# birthdaycontrol.net
KiCad netlist of a schematic drawn in EAGLE
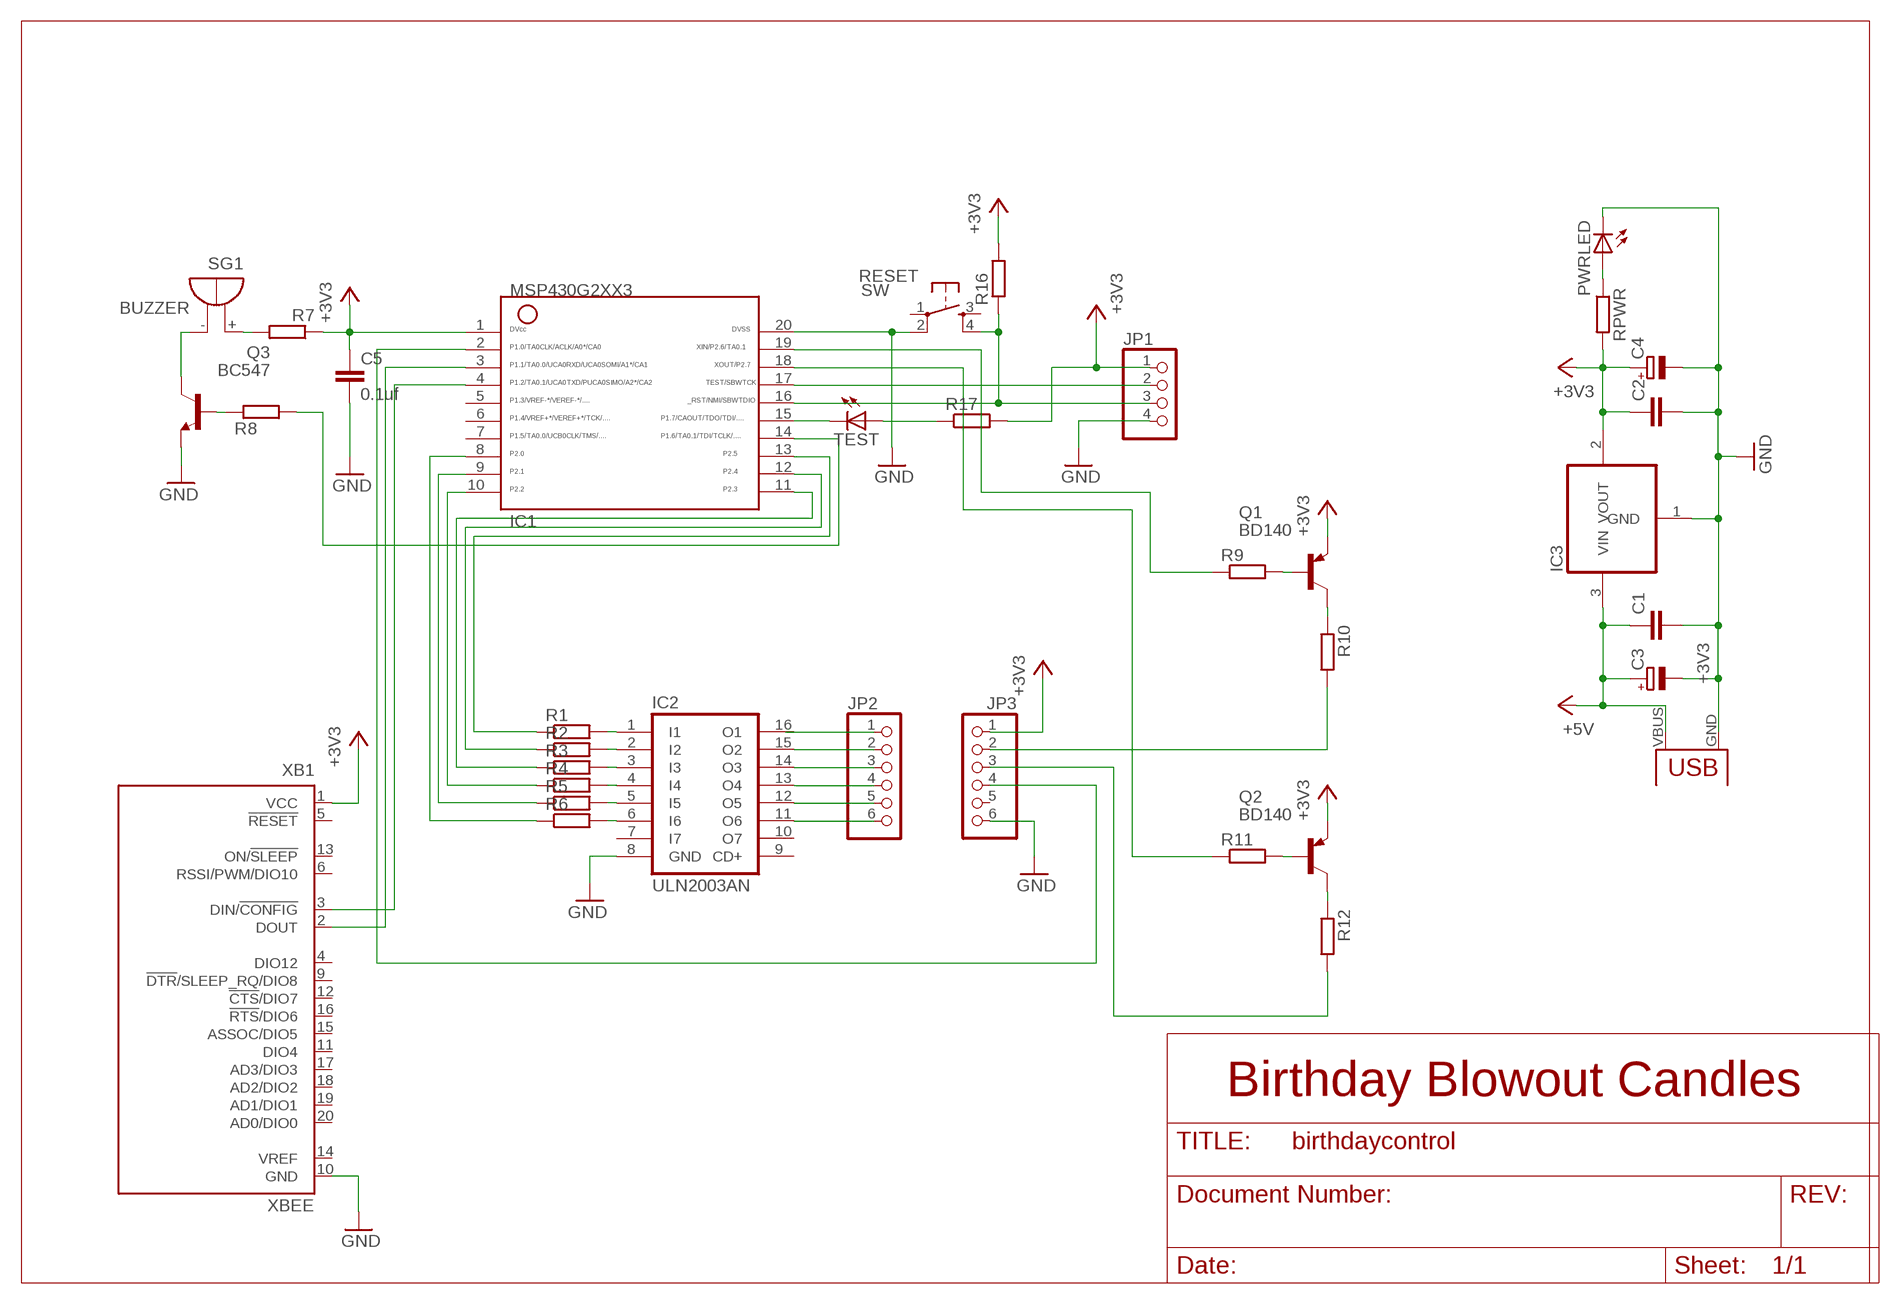
[diagram p0: schematic, sheet 1]

(export (version "E")
  (design (tool "Eeschema 10.0.6"))
  (components
    (comp (ref "C1")
      (value "C-EU025-025X050")
      (footprint "eagle-import:C025-025X050")
      (libsource (lib "eagle-import") (part "C-EU025-025X050"))
    )
    (comp (ref "C2")
      (value "C-EU025-025X050")
      (footprint "eagle-import:C025-025X050")
      (libsource (lib "eagle-import") (part "C-EU025-025X050"))
    )
    (comp (ref "C3")
      (value "CPOL-EUE2.5-5")
      (footprint "eagle-import:E2,5-5")
      (libsource (lib "eagle-import") (part "CPOL-EUE2.5-5"))
    )
    (comp (ref "C4")
      (value "CPOL-EUE2.5-5")
      (footprint "eagle-import:E2,5-5")
      (libsource (lib "eagle-import") (part "CPOL-EUE2.5-5"))
    )
    (comp (ref "C5")
      (value "0.1uf")
      (footprint "eagle-import:C025-025X050")
      (libsource (lib "eagle-import") (part "C-EU025-025X050"))
    )
    (comp (ref "IC1")
      (value "MSP430")
      (footprint "eagle-import:G2553-DIP20")
      (libsource (lib "eagle-import") (part "MSP430G2553DIP20"))
    )
    (comp (ref "IC2")
      (value "ULN2003AN")
      (footprint "eagle-import:DIL16")
      (libsource (lib "eagle-import") (part "ULN2003AN"))
    )
    (comp (ref "IC3")
      (value "REG1117")
      (footprint "eagle-import:SOT223")
      (libsource (lib "eagle-import") (part "REG1117"))
    )
    (comp (ref "JP1")
      (value "PINHD-1X4")
      (footprint "eagle-import:1X04")
      (libsource (lib "eagle-import") (part "PINHD-1X4"))
    )
    (comp (ref "JP2")
      (value "PINHD-1X6")
      (footprint "eagle-import:1X06")
      (libsource (lib "eagle-import") (part "PINHD-1X6"))
    )
    (comp (ref "JP3")
      (value "PINHD-1X6")
      (footprint "eagle-import:1X06")
      (libsource (lib "eagle-import") (part "PINHD-1X6"))
    )
    (comp (ref "PWRLED")
      (value "LED3MM")
      (footprint "eagle-import:LED3MM")
      (libsource (lib "eagle-import") (part "LED3MM"))
    )
    (comp (ref "Q1")
      (value "BD140")
      (footprint "eagle-import:TO126")
      (libsource (lib "eagle-import") (part "BD140"))
    )
    (comp (ref "Q2")
      (value "BD140")
      (footprint "eagle-import:TO126")
      (libsource (lib "eagle-import") (part "BD140"))
    )
    (comp (ref "Q3")
      (value "BC547")
      (footprint "eagle-import:TO92")
      (libsource (lib "eagle-import") (part "BC547"))
    )
    (comp (ref "R1")
      (value "R-EU_0207/7")
      (footprint "eagle-import:0207_7")
      (libsource (lib "eagle-import") (part "resistor_R-EU_0207/7"))
    )
    (comp (ref "R2")
      (value "R-EU_0207/7")
      (footprint "eagle-import:0207_7")
      (libsource (lib "eagle-import") (part "resistor_R-EU_0207/7"))
    )
    (comp (ref "R3")
      (value "R-EU_0207/7")
      (footprint "eagle-import:0207_7")
      (libsource (lib "eagle-import") (part "resistor_R-EU_0207/7"))
    )
    (comp (ref "R4")
      (value "R-EU_0207/7")
      (footprint "eagle-import:0207_7")
      (libsource (lib "eagle-import") (part "resistor_R-EU_0207/7"))
    )
    (comp (ref "R5")
      (value "R-EU_0207/7")
      (footprint "eagle-import:0207_7")
      (libsource (lib "eagle-import") (part "resistor_R-EU_0207/7"))
    )
    (comp (ref "R6")
      (value "R-EU_0207/7")
      (footprint "eagle-import:0207_7")
      (libsource (lib "eagle-import") (part "resistor_R-EU_0207/7"))
    )
    (comp (ref "R7")
      (value "R-EU_0207/7")
      (footprint "eagle-import:0207_7")
      (libsource (lib "eagle-import") (part "R-EU_0207/7"))
    )
    (comp (ref "R8")
      (value "R-EU_0207/7")
      (footprint "eagle-import:0207_7")
      (libsource (lib "eagle-import") (part "R-EU_0207/7"))
    )
    (comp (ref "R9")
      (value "R-EU_0207/7")
      (footprint "eagle-import:0207_7")
      (libsource (lib "eagle-import") (part "R-EU_0207/7"))
    )
    (comp (ref "R10")
      (value "R-EU_0207/7")
      (footprint "eagle-import:0207_7")
      (libsource (lib "eagle-import") (part "R-EU_0207/7"))
    )
    (comp (ref "R11")
      (value "R-EU_0207/7")
      (footprint "eagle-import:0207_7")
      (libsource (lib "eagle-import") (part "R-EU_0207/7"))
    )
    (comp (ref "R12")
      (value "R-EU_0207/7")
      (footprint "eagle-import:0207_7")
      (libsource (lib "eagle-import") (part "R-EU_0207/7"))
    )
    (comp (ref "R16")
      (value "R-EU_0207/7")
      (footprint "eagle-import:0207_7")
      (libsource (lib "eagle-import") (part "R-EU_0207/7"))
    )
    (comp (ref "R17")
      (value "R-EU_0207/7")
      (footprint "eagle-import:0207_7")
      (libsource (lib "eagle-import") (part "R-EU_0207/7"))
    )
    (comp (ref "RESET")
      (value "SW")
      (footprint "eagle-import:B3F-10XX")
      (libsource (lib "eagle-import") (part "OMRON_SWITCH_10-XX"))
    )
    (comp (ref "RPWR")
      (value "R-EU_0207/7")
      (footprint "eagle-import:0207_7")
      (libsource (lib "eagle-import") (part "R-EU_0207/7"))
    )
    (comp (ref "SG1")
      (value "BUZZER")
      (footprint "eagle-import:F_TMB")
      (libsource (lib "eagle-import") (part "BUZZER"))
    )
    (comp (ref "TEST")
      (value "LED3MM")
      (footprint "eagle-import:LED3MM")
      (libsource (lib "eagle-import") (part "LED3MM"))
    )
    (comp (ref "U$6")
      (value "USB(POWER)")
      (footprint "eagle-import:USB(POWER)")
      (libsource (lib "eagle-import") (part "USB(POWER)"))
    )
    (comp (ref "XB1")
      (value "XBEE")
      (footprint "eagle-import:XBEE")
      (fields (field (name "MPN") "XBP24-Z7UIT-004"))
      (libsource (lib "eagle-import") (part "XBEE"))
    )
  )
  (nets
    (net (code "1") (name "+3V3") (class "Default")
      (node (ref "C2") (pin "1") (pinfunction "1_1") (pintype "passive"))
      (node (ref "C4") (pin "+") (pinfunction "+_+") (pintype "passive"))
      (node (ref "C5") (pin "1") (pinfunction "1_1") (pintype "passive"))
      (node (ref "IC1") (pin "1") (pinfunction "1_1") (pintype "power_in"))
      (node (ref "IC3") (pin "2") (pinfunction "VOUT_2") (pintype "output"))
      (node (ref "JP1") (pin "1") (pinfunction "1_1") (pintype "passive"))
      (node (ref "JP3") (pin "1") (pinfunction "1_1") (pintype "passive"))
      (node (ref "Q1") (pin "1") (pinfunction "E_1") (pintype "passive"))
      (node (ref "Q2") (pin "1") (pinfunction "E_1") (pintype "passive"))
      (node (ref "R16") (pin "2") (pinfunction "2_2") (pintype "passive"))
      (node (ref "R17") (pin "2") (pinfunction "2_2") (pintype "passive"))
      (node (ref "R7") (pin "1") (pinfunction "1_1") (pintype "passive"))
      (node (ref "RPWR") (pin "2") (pinfunction "2_2") (pintype "passive"))
      (node (ref "XB1") (pin "1") (pinfunction "VCC_1") (pintype "power_in"))
    )
    (net (code "2") (name "+5V") (class "Default")
      (node (ref "C1") (pin "1") (pinfunction "1_1") (pintype "passive"))
      (node (ref "C3") (pin "+") (pinfunction "+_+") (pintype "passive"))
      (node (ref "IC3") (pin "3") (pinfunction "VIN_3") (pintype "input"))
      (node (ref "U$6") (pin "VBUS") (pinfunction "VCC_VBUS") (pintype "power_in"))
    )
    (net (code "3") (name "GND") (class "Default")
      (node (ref "C1") (pin "2") (pinfunction "2_2") (pintype "passive"))
      (node (ref "C2") (pin "2") (pinfunction "2_2") (pintype "passive"))
      (node (ref "C3") (pin "-") (pinfunction "-_-") (pintype "passive"))
      (node (ref "C4") (pin "-") (pinfunction "-_-") (pintype "passive"))
      (node (ref "C5") (pin "2") (pinfunction "2_2") (pintype "passive"))
      (node (ref "IC1") (pin "20") (pinfunction "20_20") (pintype "power_in"))
      (node (ref "IC2") (pin "8") (pinfunction "GND_8") (pintype "power_in"))
      (node (ref "IC3") (pin "1") (pinfunction "GND_1") (pintype "power_in"))
      (node (ref "JP1") (pin "4") (pinfunction "4_4") (pintype "passive"))
      (node (ref "JP3") (pin "6") (pinfunction "6_6") (pintype "passive"))
      (node (ref "PWRLED") (pin "K") (pinfunction "C_K") (pintype "passive"))
      (node (ref "Q3") (pin "1") (pinfunction "E_1") (pintype "passive"))
      (node (ref "RESET") (pin "2") (pinfunction "P1_2") (pintype "passive"))
      (node (ref "U$6") (pin "GND") (pinfunction "GND_GND") (pintype "power_in"))
      (node (ref "XB1") (pin "10") (pinfunction "GND_10") (pintype "power_in"))
    )
    (net (code "4") (name "Net-(IC1-Pad2)") (class "Default")
      (node (ref "IC1") (pin "2") (pinfunction "2_2") (pintype "bidirectional"))
      (node (ref "JP3") (pin "4") (pinfunction "4_4") (pintype "passive"))
    )
    (net (code "5") (name "Net-(IC1-Pad8)") (class "Default")
      (node (ref "IC1") (pin "8") (pinfunction "8_8") (pintype "bidirectional"))
      (node (ref "R6") (pin "1") (pinfunction "1_1") (pintype "passive"))
    )
    (net (code "6") (name "Net-(IC1-Pad9)") (class "Default")
      (node (ref "IC1") (pin "9") (pinfunction "9_9") (pintype "bidirectional"))
      (node (ref "R5") (pin "1") (pinfunction "1_1") (pintype "passive"))
    )
    (net (code "7") (name "Net-(IC1-Pad10)") (class "Default")
      (node (ref "IC1") (pin "10") (pinfunction "10_10") (pintype "bidirectional"))
      (node (ref "R4") (pin "1") (pinfunction "1_1") (pintype "passive"))
    )
    (net (code "8") (name "Net-(IC1-Pad11)") (class "Default")
      (node (ref "IC1") (pin "11") (pinfunction "11_11") (pintype "bidirectional"))
      (node (ref "R3") (pin "1") (pinfunction "1_1") (pintype "passive"))
    )
    (net (code "9") (name "Net-(IC1-Pad12)") (class "Default")
      (node (ref "IC1") (pin "12") (pinfunction "12_12") (pintype "bidirectional"))
      (node (ref "R2") (pin "1") (pinfunction "1_1") (pintype "passive"))
    )
    (net (code "10") (name "Net-(IC1-Pad13)") (class "Default")
      (node (ref "IC1") (pin "13") (pinfunction "13_13") (pintype "bidirectional"))
      (node (ref "R1") (pin "1") (pinfunction "1_1") (pintype "passive"))
    )
    (net (code "11") (name "Net-(IC1-Pad14)") (class "Default")
      (node (ref "IC1") (pin "14") (pinfunction "14_14") (pintype "bidirectional"))
      (node (ref "R8") (pin "2") (pinfunction "2_2") (pintype "passive"))
    )
    (net (code "12") (name "Net-(IC1-Pad17)") (class "Default")
      (node (ref "IC1") (pin "17") (pinfunction "17_17") (pintype "bidirectional"))
      (node (ref "JP1") (pin "2") (pinfunction "2_2") (pintype "passive"))
    )
    (net (code "13") (name "Net-(IC1-Pad18)") (class "Default")
      (node (ref "IC1") (pin "18") (pinfunction "18_18") (pintype "bidirectional"))
      (node (ref "R11") (pin "1") (pinfunction "1_1") (pintype "passive"))
    )
    (net (code "14") (name "Net-(IC1-Pad19)") (class "Default")
      (node (ref "IC1") (pin "19") (pinfunction "19_19") (pintype "bidirectional"))
      (node (ref "R9") (pin "1") (pinfunction "1_1") (pintype "passive"))
    )
    (net (code "15") (name "Net-(IC2-I1)") (class "Default")
      (node (ref "IC2") (pin "1") (pinfunction "I1_1") (pintype "input"))
      (node (ref "R1") (pin "2") (pinfunction "2_2") (pintype "passive"))
    )
    (net (code "16") (name "Net-(IC2-I2)") (class "Default")
      (node (ref "IC2") (pin "2") (pinfunction "I2_2") (pintype "input"))
      (node (ref "R2") (pin "2") (pinfunction "2_2") (pintype "passive"))
    )
    (net (code "17") (name "Net-(IC2-I3)") (class "Default")
      (node (ref "IC2") (pin "3") (pinfunction "I3_3") (pintype "input"))
      (node (ref "R3") (pin "2") (pinfunction "2_2") (pintype "passive"))
    )
    (net (code "18") (name "Net-(IC2-I4)") (class "Default")
      (node (ref "IC2") (pin "4") (pinfunction "I4_4") (pintype "input"))
      (node (ref "R4") (pin "2") (pinfunction "2_2") (pintype "passive"))
    )
    (net (code "19") (name "Net-(IC2-I5)") (class "Default")
      (node (ref "IC2") (pin "5") (pinfunction "I5_5") (pintype "input"))
      (node (ref "R5") (pin "2") (pinfunction "2_2") (pintype "passive"))
    )
    (net (code "20") (name "Net-(IC2-I6)") (class "Default")
      (node (ref "IC2") (pin "6") (pinfunction "I6_6") (pintype "input"))
      (node (ref "R6") (pin "2") (pinfunction "2_2") (pintype "passive"))
    )
    (net (code "21") (name "Net-(IC2-O1)") (class "Default")
      (node (ref "IC2") (pin "16") (pinfunction "O1_16") (pintype "open_collector"))
      (node (ref "JP2") (pin "1") (pinfunction "1_1") (pintype "passive"))
    )
    (net (code "22") (name "Net-(IC2-O2)") (class "Default")
      (node (ref "IC2") (pin "15") (pinfunction "O2_15") (pintype "open_collector"))
      (node (ref "JP2") (pin "2") (pinfunction "2_2") (pintype "passive"))
    )
    (net (code "23") (name "Net-(IC2-O3)") (class "Default")
      (node (ref "IC2") (pin "14") (pinfunction "O3_14") (pintype "open_collector"))
      (node (ref "JP2") (pin "3") (pinfunction "3_3") (pintype "passive"))
    )
    (net (code "24") (name "Net-(IC2-O4)") (class "Default")
      (node (ref "IC2") (pin "13") (pinfunction "O4_13") (pintype "open_collector"))
      (node (ref "JP2") (pin "4") (pinfunction "4_4") (pintype "passive"))
    )
    (net (code "25") (name "Net-(IC2-O5)") (class "Default")
      (node (ref "IC2") (pin "12") (pinfunction "O5_12") (pintype "open_collector"))
      (node (ref "JP2") (pin "5") (pinfunction "5_5") (pintype "passive"))
    )
    (net (code "26") (name "Net-(IC2-O6)") (class "Default")
      (node (ref "IC2") (pin "11") (pinfunction "O6_11") (pintype "open_collector"))
      (node (ref "JP2") (pin "6") (pinfunction "6_6") (pintype "passive"))
    )
    (net (code "27") (name "Net-(JP3-Pad2)") (class "Default")
      (node (ref "JP3") (pin "2") (pinfunction "2_2") (pintype "passive"))
      (node (ref "R10") (pin "2") (pinfunction "2_2") (pintype "passive"))
    )
    (net (code "28") (name "Net-(JP3-Pad3)") (class "Default")
      (node (ref "JP3") (pin "3") (pinfunction "3_3") (pintype "passive"))
      (node (ref "R12") (pin "2") (pinfunction "2_2") (pintype "passive"))
    )
    (net (code "29") (name "Net-(PWRLED-PadA)") (class "Default")
      (node (ref "PWRLED") (pin "A") (pinfunction "A_A") (pintype "passive"))
      (node (ref "RPWR") (pin "1") (pinfunction "1_1") (pintype "passive"))
    )
    (net (code "30") (name "Net-(Q1-B)") (class "Default")
      (node (ref "Q1") (pin "3") (pinfunction "B_3") (pintype "passive"))
      (node (ref "R9") (pin "2") (pinfunction "2_2") (pintype "passive"))
    )
    (net (code "31") (name "Net-(Q1-C)") (class "Default")
      (node (ref "Q1") (pin "2") (pinfunction "C_2") (pintype "passive"))
      (node (ref "R10") (pin "1") (pinfunction "1_1") (pintype "passive"))
    )
    (net (code "32") (name "Net-(Q2-B)") (class "Default")
      (node (ref "Q2") (pin "3") (pinfunction "B_3") (pintype "passive"))
      (node (ref "R11") (pin "2") (pinfunction "2_2") (pintype "passive"))
    )
    (net (code "33") (name "Net-(Q2-C)") (class "Default")
      (node (ref "Q2") (pin "2") (pinfunction "C_2") (pintype "passive"))
      (node (ref "R12") (pin "1") (pinfunction "1_1") (pintype "passive"))
    )
    (net (code "34") (name "Net-(Q3-B)") (class "Default")
      (node (ref "Q3") (pin "2") (pinfunction "B_2") (pintype "passive"))
      (node (ref "R8") (pin "1") (pinfunction "1_1") (pintype "passive"))
    )
    (net (code "35") (name "Net-(Q3-C)") (class "Default")
      (node (ref "Q3") (pin "3") (pinfunction "C_3") (pintype "passive"))
      (node (ref "SG1") (pin "-") (pinfunction "-_-") (pintype "passive"))
    )
    (net (code "36") (name "Net-(R7-Pad2)") (class "Default")
      (node (ref "R7") (pin "2") (pinfunction "2_2") (pintype "passive"))
      (node (ref "SG1") (pin "+") (pinfunction "+_+") (pintype "passive"))
    )
    (net (code "37") (name "Net-(R17-Pad1)") (class "Default")
      (node (ref "R17") (pin "1") (pinfunction "1_1") (pintype "passive"))
      (node (ref "TEST") (pin "A") (pinfunction "A_A") (pintype "passive"))
    )
    (net (code "38") (name "Net-(RESET-S1)") (class "Default")
      (node (ref "IC1") (pin "16") (pinfunction "16_16") (pintype "bidirectional"))
      (node (ref "JP1") (pin "3") (pinfunction "3_3") (pintype "passive"))
      (node (ref "R16") (pin "1") (pinfunction "1_1") (pintype "passive"))
      (node (ref "RESET") (pin "4") (pinfunction "S1_4") (pintype "passive"))
    )
    (net (code "39") (name "Net-(TEST-C)") (class "Default")
      (node (ref "IC1") (pin "15") (pinfunction "15_15") (pintype "bidirectional"))
      (node (ref "TEST") (pin "K") (pinfunction "C_K") (pintype "passive"))
    )
    (net (code "40") (name "Net-(XB1-DIN{slash}~{CONFIG})") (class "Default")
      (node (ref "IC1") (pin "4") (pinfunction "4_4") (pintype "bidirectional"))
      (node (ref "XB1") (pin "3") (pinfunction "DIN/~{CONFIG}_3") (pintype "input"))
    )
    (net (code "41") (name "Net-(XB1-DOUT)") (class "Default")
      (node (ref "IC1") (pin "3") (pinfunction "3_3") (pintype "bidirectional"))
      (node (ref "XB1") (pin "2") (pinfunction "DOUT_2") (pintype "output"))
    )
    (net (code "42") (name "unconnected-(IC1-Pad5)") (class "Default")
      (node (ref "IC1") (pin "5") (pinfunction "5_5") (pintype "bidirectional"))
    )
    (net (code "43") (name "unconnected-(IC1-Pad6)") (class "Default")
      (node (ref "IC1") (pin "6") (pinfunction "6_6") (pintype "bidirectional"))
    )
    (net (code "44") (name "unconnected-(IC1-Pad7)") (class "Default")
      (node (ref "IC1") (pin "7") (pinfunction "7_7") (pintype "bidirectional"))
    )
    (net (code "45") (name "unconnected-(IC2-CD+-Pad9)") (class "Default")
      (node (ref "IC2") (pin "9") (pinfunction "CD+_9") (pintype "passive"))
    )
    (net (code "46") (name "unconnected-(IC2-I7-Pad7)") (class "Default")
      (node (ref "IC2") (pin "7") (pinfunction "I7_7") (pintype "input"))
    )
    (net (code "47") (name "unconnected-(IC2-O7-Pad10)") (class "Default")
      (node (ref "IC2") (pin "10") (pinfunction "O7_10") (pintype "open_collector"))
    )
    (net (code "48") (name "unconnected-(JP3-Pad5)") (class "Default")
      (node (ref "JP3") (pin "5") (pinfunction "5_5") (pintype "passive"))
    )
    (net (code "49") (name "unconnected-(RESET-P-Pad1)") (class "Default")
      (node (ref "RESET") (pin "1") (pinfunction "P_1") (pintype "passive"))
    )
    (net (code "50") (name "unconnected-(RESET-S-Pad3)") (class "Default")
      (node (ref "RESET") (pin "3") (pinfunction "S_3") (pintype "passive"))
    )
    (net (code "51") (name "unconnected-(XB1-AD0{slash}DIO0-Pad20)") (class "Default")
      (node (ref "XB1") (pin "20") (pinfunction "AD0/DIO0_20") (pintype "bidirectional"))
    )
    (net (code "52") (name "unconnected-(XB1-AD1{slash}DIO1-Pad19)") (class "Default")
      (node (ref "XB1") (pin "19") (pinfunction "AD1/DIO1_19") (pintype "bidirectional"))
    )
    (net (code "53") (name "unconnected-(XB1-AD2{slash}DIO2-Pad18)") (class "Default")
      (node (ref "XB1") (pin "18") (pinfunction "AD2/DIO2_18") (pintype "bidirectional"))
    )
    (net (code "54") (name "unconnected-(XB1-AD3{slash}DIO3-Pad17)") (class "Default")
      (node (ref "XB1") (pin "17") (pinfunction "AD3/DIO3_17") (pintype "bidirectional"))
    )
    (net (code "55") (name "unconnected-(XB1-ASSOC{slash}DIO5-Pad15)") (class "Default")
      (node (ref "XB1") (pin "15") (pinfunction "ASSOC/DIO5_15") (pintype "bidirectional"))
    )
    (net (code "56") (name "unconnected-(XB1-DIO4-Pad11)") (class "Default")
      (node (ref "XB1") (pin "11") (pinfunction "DIO4_11") (pintype "bidirectional"))
    )
    (net (code "57") (name "unconnected-(XB1-DIO12-Pad4)") (class "Default")
      (node (ref "XB1") (pin "4") (pinfunction "DIO12_4") (pintype "bidirectional"))
    )
    (net (code "58") (name "unconnected-(XB1-ON{slash}~{SLEEP}-Pad13)") (class "Default")
      (node (ref "XB1") (pin "13") (pinfunction "ON/~{SLEEP}_13") (pintype "output"))
    )
    (net (code "59") (name "unconnected-(XB1-RSSI{slash}PWM{slash}DIO10-Pad6)") (class "Default")
      (node (ref "XB1") (pin "6") (pinfunction "RSSI/PWM/DIO10_6") (pintype "output"))
    )
    (net (code "60") (name "unconnected-(XB1-VREF-Pad14)") (class "Default")
      (node (ref "XB1") (pin "14") (pinfunction "VREF_14") (pintype "input"))
    )
    (net (code "61") (name "unconnected-(XB1-~{CTS}{slash}DIO7-Pad12)") (class "Default")
      (node (ref "XB1") (pin "12") (pinfunction "~{CTS}/DIO7_12") (pintype "bidirectional"))
    )
    (net (code "62") (name "unconnected-(XB1-~{DTR}{slash}SLEEP_RQ{slash}DIO8-Pad9)") (class "Default")
      (node (ref "XB1") (pin "9") (pinfunction "~{DTR}/SLEEP_RQ/DIO8_9") (pintype "bidirectional"))
    )
    (net (code "63") (name "unconnected-(XB1-~{RESET}-Pad5)") (class "Default")
      (node (ref "XB1") (pin "5") (pinfunction "~{RESET}_5") (pintype "input"))
    )
    (net (code "64") (name "unconnected-(XB1-~{RTS}{slash}DIO6-Pad16)") (class "Default")
      (node (ref "XB1") (pin "16") (pinfunction "~{RTS}/DIO6_16") (pintype "bidirectional"))
    )
  )
)
